# IPMC_TestBoard.net
KiCad netlist of a schematic drawn in Altium Designer
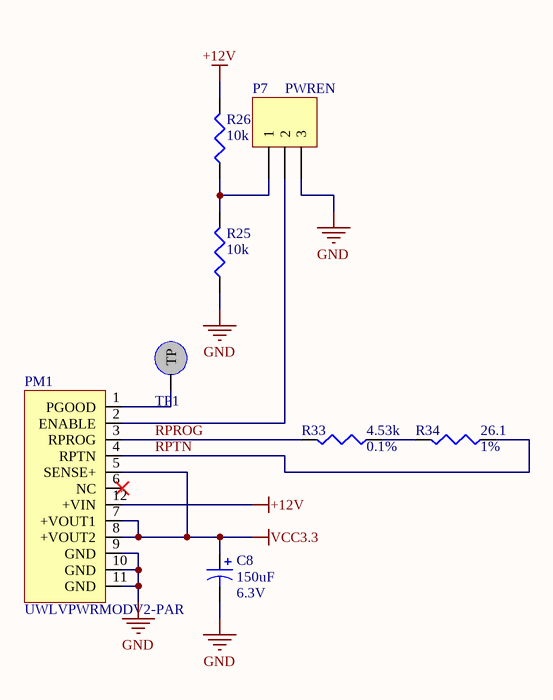
[diagram p0: IPMC_TestBoard.SchDoc]

(export (version "E")
  (design (tool "Eeschema 10.0.6"))
  (components
    (comp (ref "C8")
      (value "150uF")
      (footprint "VISH-293D-7343-31_V")
      (description "Polarized Capacitor (Surface Mount)")
      (fields
        (field (name "RATING") "6.3V")
        (field (name "MFG. PART NO.") "A700X157M006ATE015")
        (field (name "Comment") "?")
      )
      (libsource (lib "Miscellaneous Devices") (part "Cap Pol3"))
    )
    (comp (ref "P7")
      (value "PWREN")
      (footprint "HEADER1X3")
      (description "Header, 3-Pin")
      (fields (field (name "MFG. PART NO.") "?"))
      (libsource (lib "Miscellaneous Connectors") (part "Header 3"))
    )
    (comp (ref "PM1")
      (value "UWLVPWRMODV2-PAR")
      (footprint "UWLVPWRMODV2")
      (description "UW Low-voltage Power Module V2")
      (fields (field (name "MFG. PART NO.") "UWLVPWRMODV2"))
      (libsource (lib "CustomSymbols") (part "UWLVPWRMODV2-PAR"))
    )
    (comp (ref "R25")
      (value "10k")
      (footprint "R0402_IPC_H")
      (description "Resistor")
      (fields (field (name "TOLERANCE") "5%") (field (name "MFG. PART NO.") "ERJ-2GEJ103X"))
      (libsource (lib "CustomSymbols") (part "Res"))
    )
    (comp (ref "R26")
      (value "10k")
      (footprint "R0402_IPC_H")
      (description "Resistor")
      (fields (field (name "TOLERANCE") "5%") (field (name "MFG. PART NO.") "ERJ-2GEJ103X"))
      (libsource (lib "CustomSymbols") (part "Res"))
    )
    (comp (ref "R33")
      (value "4.53k")
      (footprint "R0402")
      (description "Resistor")
      (fields
        (field (name "TOLERANCE") "0.1%")
        (field (name "MFG. PART NO.") "ERA-2AEB4531X")
        (field (name "Comment") "?")
      )
      (libsource (lib "CustomSymbols") (part "Res"))
    )
    (comp (ref "R34")
      (value "26.1")
      (footprint "R0402")
      (description "Resistor")
      (fields
        (field (name "TOLERANCE") "1%")
        (field (name "MFG. PART NO.") "ERJ-2RKF26R1X")
        (field (name "Comment") "?")
      )
      (libsource (lib "CustomSymbols") (part "Res"))
    )
    (comp (ref "TP1")
      (value "TP")
      (footprint "TP")
      (description "Test Point")
      (fields (field (name "MFG. PART NO.") "NA"))
      (libsource (lib "CustomSymbols") (part "TP"))
    )
  )
  (nets
    (net (code "1") (name "+12V") (class "Default")
      (node (ref "PM1") (pin "12") (pinfunction "+VIN_12") (pintype "passive"))
      (node (ref "R26") (pin "2") (pinfunction "2_2") (pintype "passive"))
    )
    (net (code "2") (name "/RPROG") (class "Default")
      (node (ref "PM1") (pin "3") (pinfunction "RPROG_3") (pintype "passive"))
      (node (ref "R33") (pin "2") (pinfunction "2_2") (pintype "passive"))
    )
    (net (code "3") (name "/RPTN") (class "Default")
      (node (ref "PM1") (pin "4") (pinfunction "RPTN_4") (pintype "passive"))
      (node (ref "R34") (pin "1") (pinfunction "1_1") (pintype "passive"))
    )
    (net (code "4") (name "GND") (class "Default")
      (node (ref "C8") (pin "2") (pinfunction "2_2") (pintype "passive"))
      (node (ref "P7") (pin "3") (pinfunction "3_3") (pintype "passive"))
      (node (ref "PM1") (pin "10") (pinfunction "GND_10") (pintype "passive"))
      (node (ref "PM1") (pin "11") (pinfunction "GND_11") (pintype "passive"))
      (node (ref "PM1") (pin "9") (pinfunction "GND_9") (pintype "passive"))
      (node (ref "R25") (pin "1") (pinfunction "1_1") (pintype "passive"))
    )
    (net (code "5") (name "Net-(P7-Pad1)") (class "Default")
      (node (ref "P7") (pin "1") (pinfunction "1_1") (pintype "passive"))
      (node (ref "R25") (pin "2") (pinfunction "2_2") (pintype "passive"))
      (node (ref "R26") (pin "1") (pinfunction "1_1") (pintype "passive"))
    )
    (net (code "6") (name "Net-(PM1-ENABLE)") (class "Default")
      (node (ref "P7") (pin "2") (pinfunction "2_2") (pintype "passive"))
      (node (ref "PM1") (pin "2") (pinfunction "ENABLE_2") (pintype "passive"))
    )
    (net (code "7") (name "Net-(PM1-PGOOD)") (class "Default")
      (node (ref "PM1") (pin "1") (pinfunction "PGOOD_1") (pintype "passive"))
      (node (ref "TP1") (pin "1") (pinfunction "TP_1") (pintype "passive"))
    )
    (net (code "8") (name "Net-(R33-Pad1)") (class "Default")
      (node (ref "R33") (pin "1") (pinfunction "1_1") (pintype "passive"))
      (node (ref "R34") (pin "2") (pinfunction "2_2") (pintype "passive"))
    )
    (net (code "9") (name "VCC3.3") (class "Default")
      (node (ref "C8") (pin "1") (pinfunction "1_1") (pintype "passive"))
      (node (ref "PM1") (pin "5") (pinfunction "SENSE+_5") (pintype "passive"))
      (node (ref "PM1") (pin "7") (pinfunction "+VOUT1_7") (pintype "passive"))
      (node (ref "PM1") (pin "8") (pinfunction "+VOUT2_8") (pintype "passive"))
    )
    (net (code "10") (name "unconnected-(PM1-NC-Pad6)") (class "Default")
      (node (ref "PM1") (pin "6") (pinfunction "NC_6") (pintype "passive+no_connect"))
    )
  )
)
